# Sheet_ionode.net
KiCad netlist of a schematic drawn in Altium Designer
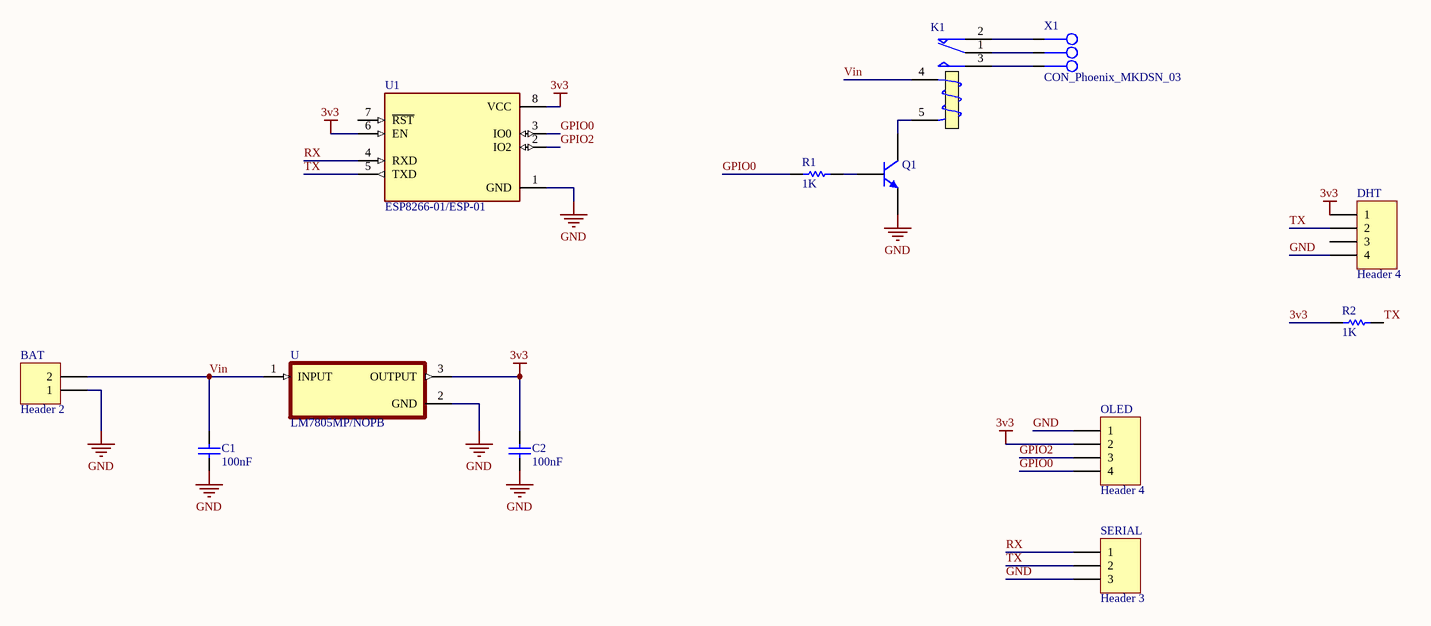
[diagram p0: Sheet ionode.SchDoc]

(export (version "E")
  (design (tool "Eeschema 10.0.6"))
  (components
    (comp (ref "BAT")
      (value "Header 2")
      (footprint "HDR1X2")
      (description "Header, 2-Pin")
      (fields (field (name "PUBLISHER") "Altium Limited"))
      (libsource (lib "Miscellaneous Connectors") (part "Header 2"))
    )
    (comp (ref "C1")
      (value "100nF")
      (footprint "CAP1206")
      (description "TOTAL CAPACITOR SMD PACK")
      (fields (field (name "DESIGNER") "Abbas Basereh"))
      (libsource (lib "Altium") (part "CAP SMD PACKAGE"))
    )
    (comp (ref "C2")
      (value "100nF")
      (footprint "CAP1206")
      (description "TOTAL CAPACITOR SMD PACK")
      (fields (field (name "DESIGNER") "Abbas Basereh"))
      (libsource (lib "Altium") (part "CAP SMD PACKAGE"))
    )
    (comp (ref "DHT")
      (value "Header 4")
      (footprint "HDR1X4")
      (description "Header, 4-Pin")
      (fields (field (name "PUBLISHER") "Altium Limited"))
      (libsource (lib "Miscellaneous Connectors") (part "Header 4"))
    )
    (comp (ref "K1")
      (value "~")
      (footprint "Relay 18.85x15.35x15.70")
      (description "Single-Pole Dual-Throw Relay")
      (fields (field (name "DESIGNER") "Abbas Basereh"))
      (libsource (lib "Altium") (part "RELAY_SPDT"))
    )
    (comp (ref "OLED")
      (value "Header 4")
      (footprint "HDR1X4")
      (description "Header, 4-Pin")
      (fields (field (name "PUBLISHER") "Altium Limited"))
      (libsource (lib "Miscellaneous Connectors") (part "Header 4"))
    )
    (comp (ref "Q1")
      (value "~")
      (footprint "SOT23_N")
      (description "NPN General Purpose Amplifier")
      (fields (field (name "PUBLISHER") "Altium Limited"))
      (libsource (lib "Miscellaneous Devices") (part "2N3904"))
    )
    (comp (ref "R1")
      (value "1K")
      (footprint "RESC4817X04N")
      (description "RES 1206")
      (fields (field (name "DESIGNER") "Abbas Basereh"))
      (libsource (lib "Altium") (part "RES 1206 0.25W"))
    )
    (comp (ref "R2")
      (value "1K")
      (footprint "RESC4817X04N")
      (description "RES 1206")
      (fields (field (name "DESIGNER") "Abbas Basereh"))
      (libsource (lib "Altium") (part "RES 1206 0.25W"))
    )
    (comp (ref "SERIAL")
      (value "Header 3")
      (footprint "HDR1X3")
      (description "Header, 3-Pin")
      (fields (field (name "PUBLISHER") "Altium Limited"))
      (libsource (lib "Miscellaneous Connectors") (part "Header 3"))
    )
    (comp (ref "U")
      (value "LM7805MP/NOPB")
      (footprint "SOT230P700X180-4N")
      (description "1.5-A, Wide VIN Fixed Voltage Regulators")
      (fields (field (name "MF") "Texas Instruments"))
      (libsource (lib "LM7805MP_NOPB") (part "LM7805MP/NOPB"))
    )
    (comp (ref "U1")
      (value "ESP8266-01/ESP-01")
      (footprint "XCVR_ESP8266-01/ESP-01")
      (fields (field (name "MF") "AI-Thinker"))
      (libsource (lib "ESP8266-01_ESP-01") (part "ESP8266-01/ESP-01"))
    )
    (comp (ref "X1")
      (value "CON_Phoenix_MKDSN_03")
      (footprint "CON_MKDSN1,5/3-5,08")
      (fields
        (field (name "MANUFACTURER") "PHOENIX CONTACT")
        (field (name "VOLTAGE") "400 V")
        (field (name "DESIGNER") "Eng. Saeid Jorablo")
        (field (name "PUBLISHER") "SJ UnLimited")
      )
      (libsource (lib "Sockets And Connectors") (part "CON_Phoenix_MKDSN_03"))
    )
  )
  (nets
    (net (code "1") (name "/GPIO0") (class "Default")
      (node (ref "OLED") (pin "4") (pinfunction "4_4") (pintype "passive"))
      (node (ref "R1") (pin "1") (pinfunction "1_1") (pintype "passive"))
      (node (ref "U1") (pin "3") (pinfunction "IO0_3") (pintype "bidirectional"))
    )
    (net (code "2") (name "/GPIO2") (class "Default")
      (node (ref "OLED") (pin "3") (pinfunction "3_3") (pintype "passive"))
      (node (ref "U1") (pin "2") (pinfunction "IO2_2") (pintype "bidirectional"))
    )
    (net (code "3") (name "/RX") (class "Default")
      (node (ref "SERIAL") (pin "1") (pinfunction "1_1") (pintype "passive"))
      (node (ref "U1") (pin "4") (pinfunction "RXD_4") (pintype "input"))
    )
    (net (code "4") (name "/TX") (class "Default")
      (node (ref "DHT") (pin "2") (pinfunction "2_2") (pintype "passive"))
      (node (ref "R2") (pin "2") (pinfunction "2_2") (pintype "passive"))
      (node (ref "SERIAL") (pin "2") (pinfunction "2_2") (pintype "passive"))
      (node (ref "U1") (pin "5") (pinfunction "TXD_5") (pintype "output"))
    )
    (net (code "5") (name "/Vin") (class "Default")
      (node (ref "BAT") (pin "2") (pinfunction "2_2") (pintype "passive"))
      (node (ref "C1") (pin "2") (pinfunction "2_2") (pintype "passive"))
      (node (ref "K1") (pin "4") (pinfunction "T1_4") (pintype "passive"))
      (node (ref "U") (pin "1") (pinfunction "INPUT_1") (pintype "input"))
    )
    (net (code "6") (name "3v3") (class "Default")
      (node (ref "C2") (pin "2") (pinfunction "2_2") (pintype "passive"))
      (node (ref "DHT") (pin "1") (pinfunction "1_1") (pintype "passive"))
      (node (ref "OLED") (pin "2") (pinfunction "2_2") (pintype "passive"))
      (node (ref "R2") (pin "1") (pinfunction "1_1") (pintype "passive"))
      (node (ref "U") (pin "3") (pinfunction "OUTPUT_3") (pintype "output"))
      (node (ref "U1") (pin "6") (pinfunction "EN_6") (pintype "input"))
      (node (ref "U1") (pin "8") (pinfunction "VCC_8") (pintype "power_in"))
    )
    (net (code "7") (name "GND") (class "Default")
      (node (ref "BAT") (pin "1") (pinfunction "1_1") (pintype "passive"))
      (node (ref "C1") (pin "1") (pinfunction "1_1") (pintype "passive"))
      (node (ref "C2") (pin "1") (pinfunction "1_1") (pintype "passive"))
      (node (ref "DHT") (pin "4") (pinfunction "4_4") (pintype "passive"))
      (node (ref "OLED") (pin "1") (pinfunction "1_1") (pintype "passive"))
      (node (ref "Q1") (pin "3") (pinfunction "C_3") (pintype "passive"))
      (node (ref "SERIAL") (pin "3") (pinfunction "3_3") (pintype "passive"))
      (node (ref "U") (pin "2") (pinfunction "GND_2") (pintype "power_in"))
      (node (ref "U1") (pin "1") (pinfunction "GND_1") (pintype "power_in"))
    )
    (net (code "8") (name "Net-(K1-COM)") (class "Default")
      (node (ref "K1") (pin "1") (pinfunction "COM_1") (pintype "passive"))
      (node (ref "X1") (pin "2") (pinfunction "2_2") (pintype "passive"))
    )
    (net (code "9") (name "Net-(K1-NC)") (class "Default")
      (node (ref "K1") (pin "2") (pinfunction "NC_2") (pintype "passive"))
      (node (ref "X1") (pin "1") (pinfunction "1_1") (pintype "passive"))
    )
    (net (code "10") (name "Net-(K1-NO)") (class "Default")
      (node (ref "K1") (pin "3") (pinfunction "NO_3") (pintype "passive"))
      (node (ref "X1") (pin "3") (pinfunction "3_3") (pintype "passive"))
    )
    (net (code "11") (name "Net-(K1-T2)") (class "Default")
      (node (ref "K1") (pin "5") (pinfunction "T2_5") (pintype "passive"))
      (node (ref "Q1") (pin "2") (pinfunction "B_2") (pintype "passive"))
    )
    (net (code "12") (name "Net-(Q1-E)") (class "Default")
      (node (ref "Q1") (pin "1") (pinfunction "E_1") (pintype "passive"))
      (node (ref "R1") (pin "2") (pinfunction "2_2") (pintype "passive"))
    )
    (net (code "13") (name "unconnected-(DHT-Pad3)") (class "Default")
      (node (ref "DHT") (pin "3") (pinfunction "3_3") (pintype "passive"))
    )
    (net (code "14") (name "unconnected-(U1-~{RST}-Pad7)") (class "Default")
      (node (ref "U1") (pin "7") (pinfunction "~{RST}_7") (pintype "input"))
    )
  )
)
